# SKAARDUINO_v4_1.net
KiCad netlist of a schematic drawn in EAGLE
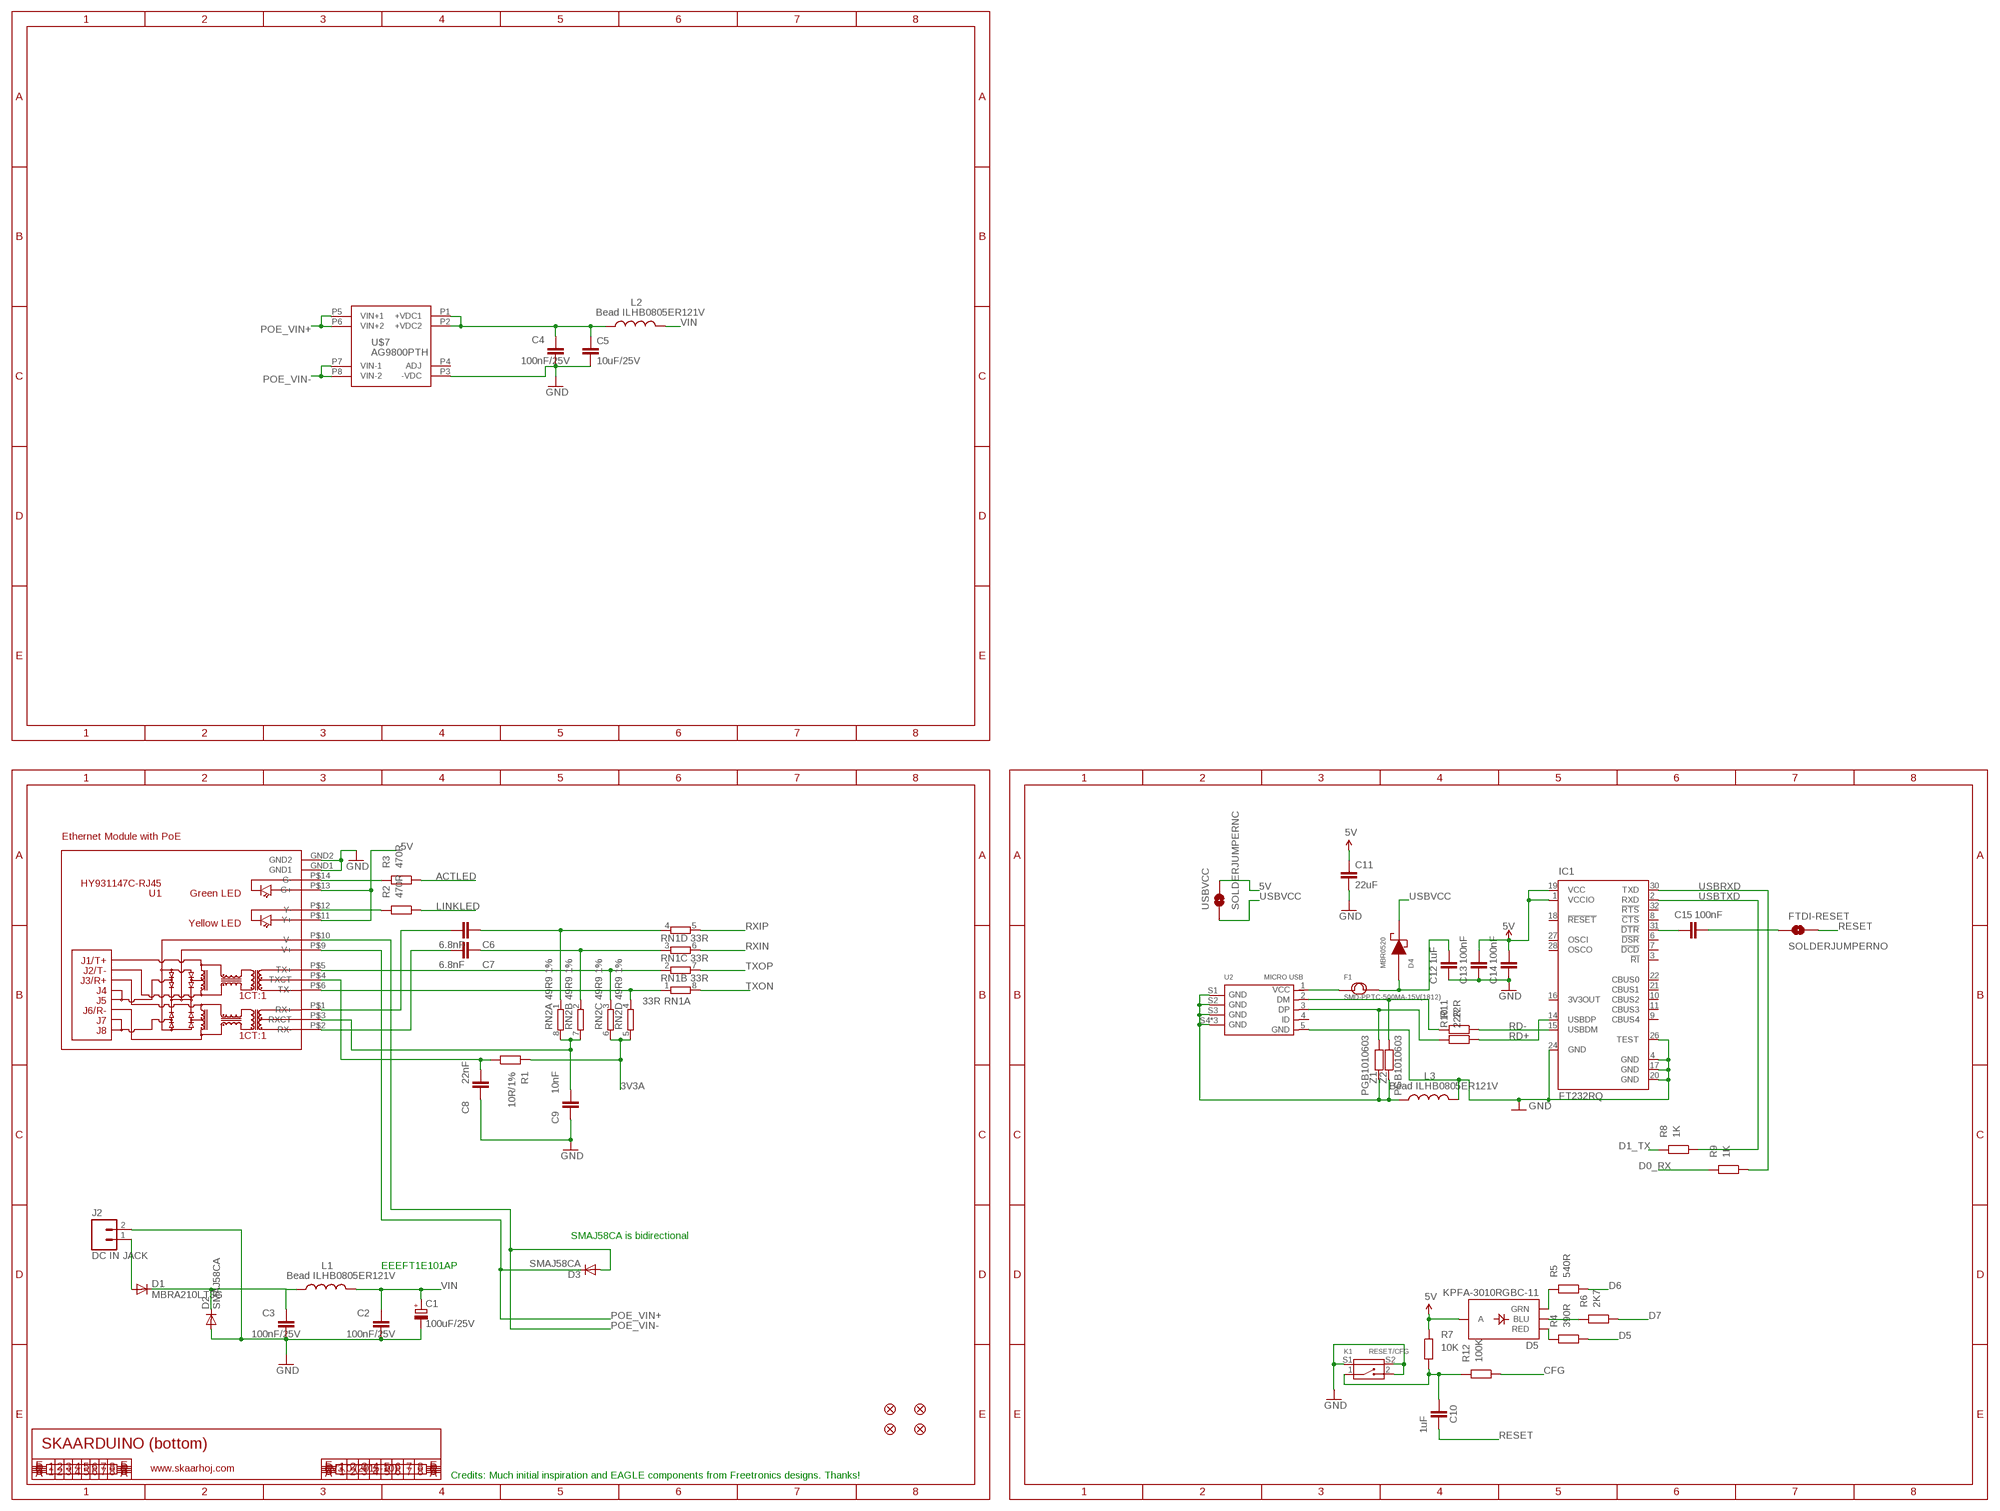
[diagram p0: schematic, sheet 1]
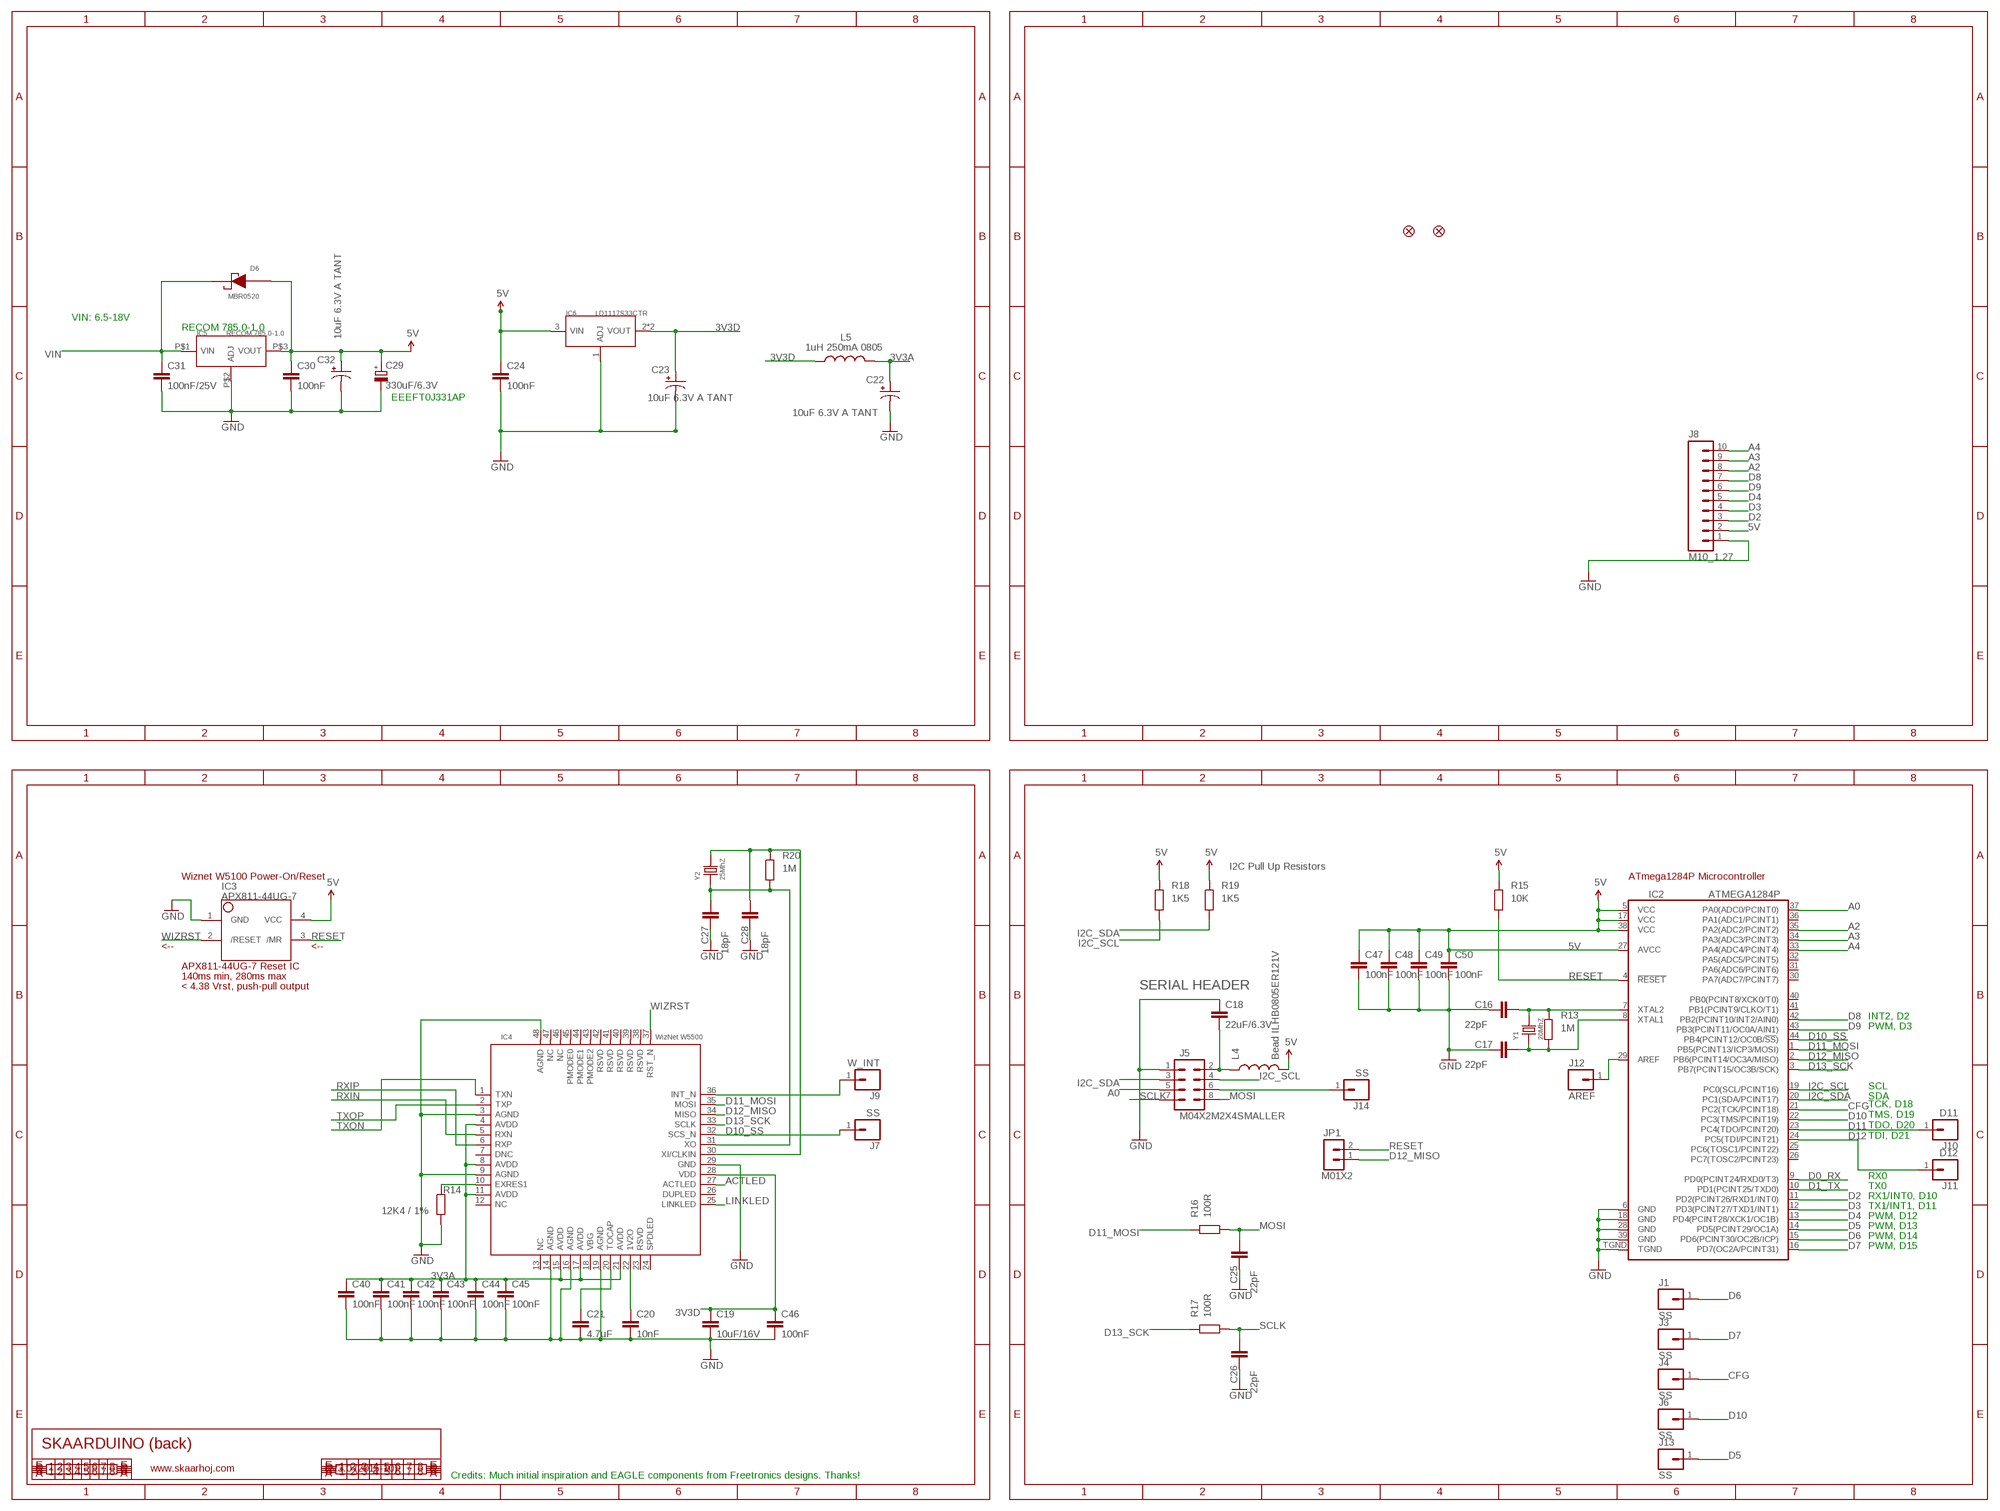
[diagram p1: schematic, sheet 2]

(export (version "E")
  (design (tool "Eeschema 10.0.6"))
  (components
    (comp (ref "C1")
      (value "100uF/25V")
      (footprint "eagle-import:PANASONIC_D")
      (libsource (lib "eagle-import") (part "CPOL-EUD"))
    )
    (comp (ref "C2")
      (value "100nF/25V")
      (footprint "eagle-import:C0402")
      (libsource (lib "eagle-import") (part "CAP0402"))
    )
    (comp (ref "C3")
      (value "100nF/25V")
      (footprint "eagle-import:C0402")
      (libsource (lib "eagle-import") (part "CAP0402"))
    )
    (comp (ref "C4")
      (value "100nF/25V")
      (footprint "eagle-import:C0402")
      (libsource (lib "eagle-import") (part "CAP0402"))
    )
    (comp (ref "C5")
      (value "10uF/25V")
      (footprint "eagle-import:0805")
      (libsource (lib "eagle-import") (part "CAP0805"))
    )
    (comp (ref "C6")
      (value "6.8nF")
      (footprint "eagle-import:0402C")
      (libsource (lib "eagle-import") (part "C-EU0402C"))
    )
    (comp (ref "C7")
      (value "6.8nF")
      (footprint "eagle-import:0402C")
      (libsource (lib "eagle-import") (part "C-EU0402C"))
    )
    (comp (ref "C8")
      (value "22nF")
      (footprint "eagle-import:0402C")
      (libsource (lib "eagle-import") (part "C-EU0402C"))
    )
    (comp (ref "C9")
      (value "10nF")
      (footprint "eagle-import:0402C")
      (libsource (lib "eagle-import") (part "C-EU0402C"))
    )
    (comp (ref "C10")
      (value "1uF")
      (footprint "eagle-import:0402C")
      (libsource (lib "eagle-import") (part "C-EU0402C"))
    )
    (comp (ref "C11")
      (value "22uF")
      (footprint "eagle-import:0805")
      (libsource (lib "eagle-import") (part "CAP0805"))
    )
    (comp (ref "C12")
      (value "1uF")
      (footprint "eagle-import:0402C")
      (libsource (lib "eagle-import") (part "C-EU0402C"))
    )
    (comp (ref "C13")
      (value "100nF")
      (footprint "eagle-import:0402C")
      (libsource (lib "eagle-import") (part "C-EU0402C"))
    )
    (comp (ref "C14")
      (value "100nF")
      (footprint "eagle-import:0402C")
      (libsource (lib "eagle-import") (part "C-EU0402C"))
    )
    (comp (ref "C15")
      (value "100nF")
      (footprint "eagle-import:0402C")
      (libsource (lib "eagle-import") (part "C-EU0402C"))
    )
    (comp (ref "D1")
      (value "MBRA210LT3G")
      (footprint "eagle-import:SMA-DIODE")
      (libsource (lib "eagle-import") (part "DIODESMA"))
    )
    (comp (ref "D2")
      (value "SMAJ58CA")
      (footprint "eagle-import:SMA-DIODE")
      (libsource (lib "eagle-import") (part "DIODESMA"))
    )
    (comp (ref "D3")
      (value "SMAJ58CA")
      (footprint "eagle-import:SMA-DIODE")
      (libsource (lib "eagle-import") (part "DIODESMA"))
    )
    (comp (ref "D4")
      (value "MBR0520")
      (footprint "eagle-import:SOD-123")
      (libsource (lib "eagle-import") (part "MBR0520"))
    )
    (comp (ref "D5")
      (value "KPFA-3010RGBC-11")
      (footprint "eagle-import:LED-TRICOLOR-SMD")
      (libsource (lib "eagle-import") (part "LED-TRICOLOR"))
    )
    (comp (ref "F1")
      (value "SMD-PPTC-500MA-15V(1812)")
      (footprint "eagle-import:F1812")
      (libsource (lib "eagle-import") (part "SMD-PPTC-500MA-15V(1812)"))
    )
    (comp (ref "FID1")
      (value "FIDUCIAL1X2.5")
      (footprint "eagle-import:FIDUCIAL-1X2.5")
      (libsource (lib "eagle-import") (part "FIDUCIAL1X2.5"))
    )
    (comp (ref "FID2")
      (value "FIDUCIAL1X2.5")
      (footprint "eagle-import:FIDUCIAL-1X2.5")
      (libsource (lib "eagle-import") (part "FIDUCIAL1X2.5"))
    )
    (comp (ref "FID3")
      (value "FIDUCIAL1X2.5")
      (footprint "eagle-import:FIDUCIAL-1X2.5")
      (libsource (lib "eagle-import") (part "FIDUCIAL1X2.5"))
    )
    (comp (ref "FID4")
      (value "FIDUCIAL1X2.5")
      (footprint "eagle-import:FIDUCIAL-1X2.5")
      (libsource (lib "eagle-import") (part "FIDUCIAL1X2.5"))
    )
    (comp (ref "FTDI-RESET")
      (value "SOLDERJUMPERNO")
      (footprint "eagle-import:SJ_2S-NO")
      (libsource (lib "eagle-import") (part "SOLDERJUMPERNO"))
    )
    (comp (ref "IC1")
      (value "FT232RQ")
      (footprint "eagle-import:QFN32")
      (libsource (lib "eagle-import") (part "FT232RQ"))
    )
    (comp (ref "J2")
      (value "DC IN JACK")
      (footprint "eagle-import:1X02")
      (libsource (lib "eagle-import") (part "M02PTH"))
    )
    (comp (ref "K1")
      (value "RESET/CFG")
      (footprint "eagle-import:SW4-SMD-7.0X3.5X3.5MM-90D")
      (fields (field (name "MPN") "TS-1188E"))
      (libsource (lib "eagle-import") (part "SMD-BUTTON-2+2P"))
    )
    (comp (ref "L1")
      (value "Bead ILHB0805ER121V")
      (footprint "eagle-import:L2012C")
      (libsource (lib "eagle-import") (part "L-USL2012C"))
    )
    (comp (ref "L2")
      (value "Bead ILHB0805ER121V")
      (footprint "eagle-import:L2012C")
      (libsource (lib "eagle-import") (part "L-USL2012C"))
    )
    (comp (ref "L3")
      (value "Bead ILHB0805ER121V")
      (footprint "eagle-import:L2012C")
      (libsource (lib "eagle-import") (part "L-USL2012C"))
    )
    (comp (ref "R1")
      (value "10R/1%")
      (footprint "eagle-import:0402")
      (libsource (lib "eagle-import") (part "freetronics-jon_RESISTOR0402"))
    )
    (comp (ref "R2")
      (value "470R")
      (footprint "eagle-import:0402")
      (libsource (lib "eagle-import") (part "freetronics-jon_RESISTOR0402"))
    )
    (comp (ref "R3")
      (value "470R")
      (footprint "eagle-import:0402")
      (libsource (lib "eagle-import") (part "freetronics-jon_RESISTOR0402"))
    )
    (comp (ref "R4")
      (value "390R")
      (footprint "eagle-import:0402")
      (libsource (lib "eagle-import") (part "freetronics-jon_RESISTOR0402"))
    )
    (comp (ref "R5")
      (value "540R")
      (footprint "eagle-import:0402")
      (libsource (lib "eagle-import") (part "freetronics-jon_RESISTOR0402"))
    )
    (comp (ref "R6")
      (value "2K7")
      (footprint "eagle-import:0402")
      (libsource (lib "eagle-import") (part "freetronics-jon_RESISTOR0402"))
    )
    (comp (ref "R7")
      (value "10K")
      (footprint "eagle-import:0402")
      (libsource (lib "eagle-import") (part "freetronics-jon_RESISTOR0402"))
    )
    (comp (ref "R8")
      (value "1K")
      (footprint "eagle-import:0402")
      (libsource (lib "eagle-import") (part "freetronics-jon_RESISTOR0402"))
    )
    (comp (ref "R9")
      (value "1K")
      (footprint "eagle-import:0402")
      (libsource (lib "eagle-import") (part "freetronics-jon_RESISTOR0402"))
    )
    (comp (ref "R10")
      (value "22R")
      (footprint "eagle-import:0402")
      (libsource (lib "eagle-import") (part "freetronics-jon_RESISTOR0402"))
    )
    (comp (ref "R11")
      (value "22R")
      (footprint "eagle-import:0402")
      (libsource (lib "eagle-import") (part "freetronics-jon_RESISTOR0402"))
    )
    (comp (ref "R12")
      (value "100K")
      (footprint "eagle-import:0402")
      (libsource (lib "eagle-import") (part "freetronics-jon_RESISTOR0402"))
    )
    (comp (ref "RN1")
      (value "33R")
      (footprint "eagle-import:CAY16")
      (libsource (lib "eagle-import") (part "4R-NCAY16"))
    )
    (comp (ref "RN2")
      (value "49R9 1%")
      (footprint "eagle-import:CAY16")
      (libsource (lib "eagle-import") (part "4R-NCAY16"))
    )
    (comp (ref "U$7")
      (value "AG9800PTH")
      (footprint "eagle-import:AG9800PTH")
      (libsource (lib "eagle-import") (part "AG9800PTH"))
    )
    (comp (ref "U1")
      (value "HY931147C-RJ45")
      (footprint "eagle-import:HY931147C")
      (libsource (lib "eagle-import") (part "HY931147C-RJ45"))
    )
    (comp (ref "U2")
      (value "MICRO USB")
      (footprint "eagle-import:MICRO-USB5+4P-SMD-0.65-B")
      (fields (field (name "MPN") "ST-USB-001G"))
      (libsource (lib "eagle-import") (part "MICRO-USB-SMD-B-WITHOUT-POST-W/P(ST-USB-001G)"))
    )
    (comp (ref "USBVCC")
      (value "SOLDERJUMPERNC")
      (footprint "eagle-import:SJ_2S")
      (libsource (lib "eagle-import") (part "SOLDERJUMPERNC"))
    )
    (comp (ref "Z1")
      (value "PGB1010603")
      (footprint "eagle-import:C0402")
      (libsource (lib "eagle-import") (part "RESISTOR0402"))
    )
    (comp (ref "Z2")
      (value "PGB1010603")
      (footprint "eagle-import:C0402")
      (libsource (lib "eagle-import") (part "RESISTOR0402"))
    )
    (comp (ref "C16")
      (value "22pF")
      (footprint "eagle-import:0402C")
      (libsource (lib "eagle-import") (part "C-EU0402C"))
    )
    (comp (ref "C17")
      (value "22pF")
      (footprint "eagle-import:0402C")
      (libsource (lib "eagle-import") (part "C-EU0402C"))
    )
    (comp (ref "C18")
      (value "22uF/6.3V")
      (footprint "eagle-import:0805")
      (libsource (lib "eagle-import") (part "CAP0805"))
    )
    (comp (ref "C19")
      (value "10uF/16V")
      (footprint "eagle-import:0805")
      (libsource (lib "eagle-import") (part "CAP0805"))
    )
    (comp (ref "C20")
      (value "10nF")
      (footprint "eagle-import:0402C")
      (libsource (lib "eagle-import") (part "C-EU0402C"))
    )
    (comp (ref "C21")
      (value "4.7uF")
      (footprint "eagle-import:0805")
      (libsource (lib "eagle-import") (part "CAP0805"))
    )
    (comp (ref "C22")
      (value "10uF 6.3V A TANT")
      (footprint "eagle-import:EIA3216")
      (libsource (lib "eagle-import") (part "CAP_POL1206"))
    )
    (comp (ref "C23")
      (value "10uF 6.3V A TANT")
      (footprint "eagle-import:EIA3216")
      (libsource (lib "eagle-import") (part "CAP_POL1206"))
    )
    (comp (ref "C24")
      (value "100nF")
      (footprint "eagle-import:0402C")
      (libsource (lib "eagle-import") (part "C-EU0402C"))
    )
    (comp (ref "C25")
      (value "22pF")
      (footprint "eagle-import:0402C")
      (libsource (lib "eagle-import") (part "C-EU0402C"))
    )
    (comp (ref "C26")
      (value "22pF")
      (footprint "eagle-import:0402C")
      (libsource (lib "eagle-import") (part "C-EU0402C"))
    )
    (comp (ref "C27")
      (value "18pF")
      (footprint "eagle-import:0402C")
      (libsource (lib "eagle-import") (part "C-EU0402C"))
    )
    (comp (ref "C28")
      (value "18pF")
      (footprint "eagle-import:0402C")
      (libsource (lib "eagle-import") (part "C-EU0402C"))
    )
    (comp (ref "C29")
      (value "330uF/6.3V")
      (footprint "eagle-import:PANASONIC_D")
      (libsource (lib "eagle-import") (part "CPOL-EUD"))
    )
    (comp (ref "C30")
      (value "100nF")
      (footprint "eagle-import:0402C")
      (libsource (lib "eagle-import") (part "C-EU0402C"))
    )
    (comp (ref "C31")
      (value "100nF/25V")
      (footprint "eagle-import:0402C")
      (libsource (lib "eagle-import") (part "C-EU0402C"))
    )
    (comp (ref "C32")
      (value "10uF 6.3V A TANT")
      (footprint "eagle-import:EIA3216")
      (libsource (lib "eagle-import") (part "CAP_POL1206"))
    )
    (comp (ref "C40")
      (value "100nF")
      (footprint "eagle-import:0402C")
      (libsource (lib "eagle-import") (part "C-EU0402C"))
    )
    (comp (ref "C41")
      (value "100nF")
      (footprint "eagle-import:0402C")
      (libsource (lib "eagle-import") (part "C-EU0402C"))
    )
    (comp (ref "C42")
      (value "100nF")
      (footprint "eagle-import:0402C")
      (libsource (lib "eagle-import") (part "C-EU0402C"))
    )
    (comp (ref "C43")
      (value "100nF")
      (footprint "eagle-import:0402C")
      (libsource (lib "eagle-import") (part "C-EU0402C"))
    )
    (comp (ref "C44")
      (value "100nF")
      (footprint "eagle-import:0402C")
      (libsource (lib "eagle-import") (part "C-EU0402C"))
    )
    (comp (ref "C45")
      (value "100nF")
      (footprint "eagle-import:0402C")
      (libsource (lib "eagle-import") (part "C-EU0402C"))
    )
    (comp (ref "C46")
      (value "100nF")
      (footprint "eagle-import:0402C")
      (libsource (lib "eagle-import") (part "C-EU0402C"))
    )
    (comp (ref "C47")
      (value "100nF")
      (footprint "eagle-import:0402C")
      (libsource (lib "eagle-import") (part "C-EU0402C"))
    )
    (comp (ref "C48")
      (value "100nF")
      (footprint "eagle-import:0402C")
      (libsource (lib "eagle-import") (part "C-EU0402C"))
    )
    (comp (ref "C49")
      (value "100nF")
      (footprint "eagle-import:0402C")
      (libsource (lib "eagle-import") (part "C-EU0402C"))
    )
    (comp (ref "C50")
      (value "100nF")
      (footprint "eagle-import:0402C")
      (libsource (lib "eagle-import") (part "C-EU0402C"))
    )
    (comp (ref "D6")
      (value "MBR0520")
      (footprint "eagle-import:SOD-123")
      (libsource (lib "eagle-import") (part "MBR0520"))
    )
    (comp (ref "FID5")
      (value "FIDUCIAL1X2.5")
      (footprint "eagle-import:FIDUCIAL-1X2.5")
      (libsource (lib "eagle-import") (part "FIDUCIAL1X2.5"))
    )
    (comp (ref "FID8")
      (value "FIDUCIAL1X2.5")
      (footprint "eagle-import:FIDUCIAL-1X2.5")
      (libsource (lib "eagle-import") (part "FIDUCIAL1X2.5"))
    )
    (comp (ref "IC2")
      (value "ATMEGA1284P")
      (footprint "eagle-import:QFN-44M1")
      (libsource (lib "eagle-import") (part "ATMEGA1284P"))
    )
    (comp (ref "IC3")
      (value "APX811-44UG-7")
      (footprint "eagle-import:SOT143-R")
      (libsource (lib "eagle-import") (part "APX81X-RESET-IC"))
    )
    (comp (ref "IC4")
      (value "WizNet W5500")
      (footprint "eagle-import:LQFP-48")
      (libsource (lib "eagle-import") (part "DRIVER-W5500"))
    )
    (comp (ref "IC5")
      (value "RECOM 785.0-1.0")
      (footprint "eagle-import:RECOM_785.0-1.0")
      (libsource (lib "eagle-import") (part "PMIC-LM317EMP"))
    )
    (comp (ref "IC6")
      (value "LD1117S33CTR")
      (footprint "eagle-import:SOT-223")
      (libsource (lib "eagle-import") (part "PMIC-LM317EMP-310030006"))
    )
    (comp (ref "J1")
      (value "SS")
      (footprint "eagle-import:M1X1")
      (libsource (lib "eagle-import") (part "M1X1TEST"))
    )
    (comp (ref "J3")
      (value "SS")
      (footprint "eagle-import:M1X1")
      (libsource (lib "eagle-import") (part "M1X1TEST"))
    )
    (comp (ref "J4")
      (value "SS")
      (footprint "eagle-import:M1X1")
      (libsource (lib "eagle-import") (part "M1X1TEST"))
    )
    (comp (ref "J5")
      (value "M04X2M2X4SMALLER")
      (footprint "eagle-import:M2X4SMALLER")
      (libsource (lib "eagle-import") (part "M04X2M2X4SMALLER"))
    )
    (comp (ref "J6")
      (value "SS")
      (footprint "eagle-import:M1X1")
      (libsource (lib "eagle-import") (part "M1X1TEST"))
    )
    (comp (ref "J7")
      (value "SS")
      (footprint "eagle-import:M1X1")
      (libsource (lib "eagle-import") (part "M1X1TEST"))
    )
    (comp (ref "J8")
      (value "M10_1.27")
      (footprint "eagle-import:M10X1")
      (libsource (lib "eagle-import") (part "M10_1.27"))
    )
    (comp (ref "J9")
      (value "W_INT")
      (footprint "eagle-import:M1X1")
      (libsource (lib "eagle-import") (part "M1X1TEST"))
    )
    (comp (ref "J10")
      (value "D11")
      (footprint "eagle-import:M1X1")
      (libsource (lib "eagle-import") (part "M1X1TEST"))
    )
    (comp (ref "J11")
      (value "D12")
      (footprint "eagle-import:M1X1")
      (libsource (lib "eagle-import") (part "M1X1TEST"))
    )
    (comp (ref "J12")
      (value "AREF")
      (footprint "eagle-import:M1X1")
      (libsource (lib "eagle-import") (part "M1X1TEST"))
    )
    (comp (ref "J13")
      (value "SS")
      (footprint "eagle-import:M1X1")
      (libsource (lib "eagle-import") (part "M1X1TEST"))
    )
    (comp (ref "J14")
      (value "SS")
      (footprint "eagle-import:M1X1")
      (libsource (lib "eagle-import") (part "M1X1TEST"))
    )
    (comp (ref "JP1")
      (value "M01X2")
      (footprint "eagle-import:M2X1SMALLER")
      (libsource (lib "eagle-import") (part "M01X2"))
    )
    (comp (ref "L4")
      (value "Bead ILHB0805ER121V")
      (footprint "eagle-import:0805")
      (libsource (lib "eagle-import") (part "INDUCTOR0805"))
    )
    (comp (ref "L5")
      (value "1uH 250mA 0805")
      (footprint "eagle-import:L2012C")
      (libsource (lib "eagle-import") (part "L-USL2012C"))
    )
    (comp (ref "R13")
      (value "1M")
      (footprint "eagle-import:0402")
      (libsource (lib "eagle-import") (part "freetronics-jon_RESISTOR0402"))
    )
    (comp (ref "R14")
      (value "12K4 / 1%")
      (footprint "eagle-import:0402")
      (libsource (lib "eagle-import") (part "freetronics-jon_RESISTOR0402"))
    )
    (comp (ref "R15")
      (value "10K")
      (footprint "eagle-import:0402")
      (libsource (lib "eagle-import") (part "freetronics-jon_RESISTOR0402"))
    )
    (comp (ref "R16")
      (value "100R")
      (footprint "eagle-import:0402")
      (libsource (lib "eagle-import") (part "freetronics-jon_RESISTOR0402"))
    )
    (comp (ref "R17")
      (value "100R")
      (footprint "eagle-import:0402")
      (libsource (lib "eagle-import") (part "freetronics-jon_RESISTOR0402"))
    )
    (comp (ref "R18")
      (value "1K5")
      (footprint "eagle-import:0402")
      (libsource (lib "eagle-import") (part "freetronics-jon_RESISTOR0402"))
    )
    (comp (ref "R19")
      (value "1K5")
      (footprint "eagle-import:0402")
      (libsource (lib "eagle-import") (part "freetronics-jon_RESISTOR0402"))
    )
    (comp (ref "R20")
      (value "1M")
      (footprint "eagle-import:0402")
      (libsource (lib "eagle-import") (part "freetronics-jon_RESISTOR0402"))
    )
    (comp (ref "Y1")
      (value "20MhZ")
      (footprint "eagle-import:X2-SMD-5.0X3.2X1.3MM")
      (fields (field (name "MPN") "X053201602002"))
      (libsource (lib "eagle-import") (part "SMD-CRYSTAL-16MHZ-8PF-20PPM-40R(2P-5.0X3.2MM)"))
    )
    (comp (ref "Y2")
      (value "25MhZ")
      (footprint "eagle-import:X2-SMD-5.0X3.2X1.3MM")
      (fields (field (name "MPN") "X053201602002"))
      (libsource (lib "eagle-import") (part "SMD-CRYSTAL-16MHZ-8PF-20PPM-40R(2P-5.0X3.2MM)"))
    )
  )
  (nets
    (net (code "1") (name "3V3A") (class "Default")
      (node (ref "C22") (pin "A") (pinfunction "+_A") (pintype "passive"))
      (node (ref "C40") (pin "1") (pinfunction "1_1") (pintype "passive"))
      (node (ref "C41") (pin "1") (pinfunction "1_1") (pintype "passive"))
      (node (ref "C42") (pin "1") (pinfunction "1_1") (pintype "passive"))
      (node (ref "C43") (pin "1") (pinfunction "1_1") (pintype "passive"))
      (node (ref "C44") (pin "1") (pinfunction "1_1") (pintype "passive"))
      (node (ref "C45") (pin "1") (pinfunction "1_1") (pintype "passive"))
      (node (ref "IC4") (pin "11") (pinfunction "AVDD_11") (pintype "passive"))
      (node (ref "IC4") (pin "15") (pinfunction "AVDD_15") (pintype "passive"))
      (node (ref "IC4") (pin "17") (pinfunction "AVDD_17") (pintype "passive"))
      (node (ref "IC4") (pin "21") (pinfunction "AVDD_21") (pintype "passive"))
      (node (ref "IC4") (pin "4") (pinfunction "AVDD_4") (pintype "passive"))
      (node (ref "IC4") (pin "8") (pinfunction "AVDD_8") (pintype "passive"))
      (node (ref "L5") (pin "2") (pinfunction "2_2") (pintype "passive"))
      (node (ref "R1") (pin "2") (pinfunction "2_2") (pintype "passive"))
      (node (ref "RN2") (pin "5") (pinfunction "2_5") (pintype "passive"))
      (node (ref "RN2") (pin "6") (pinfunction "2_6") (pintype "passive"))
    )
    (net (code "2") (name "3V3D") (class "Default")
      (node (ref "C19") (pin "1") (pinfunction "1_1") (pintype "passive"))
      (node (ref "C23") (pin "A") (pinfunction "+_A") (pintype "passive"))
      (node (ref "C46") (pin "1") (pinfunction "1_1") (pintype "passive"))
      (node (ref "IC4") (pin "28") (pinfunction "VDD_28") (pintype "passive"))
      (node (ref "IC6") (pin "2") (pinfunction "VOUT_2") (pintype "bidirectional"))
      (node (ref "IC6") (pin "TER") (pinfunction "VOUT_TER") (pintype "bidirectional"))
      (node (ref "L5") (pin "1") (pinfunction "1_1") (pintype "passive"))
    )
    (net (code "3") (name "5V") (class "Default")
      (node (ref "C11") (pin "1") (pinfunction "1_1") (pintype "passive"))
      (node (ref "C13") (pin "2") (pinfunction "2_2") (pintype "passive"))
      (node (ref "C14") (pin "2") (pinfunction "2_2") (pintype "passive"))
      (node (ref "C24") (pin "1") (pinfunction "1_1") (pintype "passive"))
      (node (ref "C29") (pin "+") (pinfunction "+_+") (pintype "passive"))
      (node (ref "C30") (pin "1") (pinfunction "1_1") (pintype "passive"))
      (node (ref "C32") (pin "A") (pinfunction "+_A") (pintype "passive"))
      (node (ref "C47") (pin "1") (pinfunction "1_1") (pintype "passive"))
      (node (ref "C48") (pin "1") (pinfunction "1_1") (pintype "passive"))
      (node (ref "C49") (pin "1") (pinfunction "1_1") (pintype "passive"))
      (node (ref "C50") (pin "1") (pinfunction "1_1") (pintype "passive"))
      (node (ref "D5") (pin "A") (pinfunction "A_A") (pintype "bidirectional"))
      (node (ref "D6") (pin "2") (pinfunction "AN_2") (pintype "passive"))
      (node (ref "IC1") (pin "1") (pinfunction "VCCIO_1") (pintype "power_in"))
      (node (ref "IC1") (pin "19") (pinfunction "VCC_19") (pintype "power_in"))
      (node (ref "IC2") (pin "17") (pinfunction "VCC_17") (pintype "bidirectional"))
      (node (ref "IC2") (pin "27") (pinfunction "AVCC_27") (pintype "bidirectional"))
      (node (ref "IC2") (pin "38") (pinfunction "VCC_38") (pintype "bidirectional"))
      (node (ref "IC2") (pin "5") (pinfunction "VCC_5") (pintype "bidirectional"))
      (node (ref "IC3") (pin "4") (pinfunction "VCC_4") (pintype "power_in"))
      (node (ref "IC5") (pin "P$3") (pinfunction "VOUT_P$3") (pintype "bidirectional"))
      (node (ref "IC6") (pin "3") (pinfunction "VIN_3") (pintype "bidirectional"))
      (node (ref "J8") (pin "2") (pinfunction "2_2") (pintype "passive"))
      (node (ref "L4") (pin "2") (pinfunction "2_2") (pintype "passive"))
      (node (ref "R15") (pin "2") (pinfunction "2_2") (pintype "passive"))
      (node (ref "R18") (pin "2") (pinfunction "2_2") (pintype "passive"))
      (node (ref "R19") (pin "2") (pinfunction "2_2") (pintype "passive"))
      (node (ref "R7") (pin "2") (pinfunction "2_2") (pintype "passive"))
      (node (ref "U1") (pin "P$11") (pinfunction "Y+_P$11") (pintype "bidirectional"))
      (node (ref "U1") (pin "P$13") (pinfunction "G+_P$13") (pintype "bidirectional"))
      (node (ref "USBVCC") (pin "2") (pinfunction "2_2") (pintype "passive"))
    )
    (net (code "4") (name "A0") (class "Default")
      (node (ref "IC2") (pin "37") (pinfunction "PA0(ADC0/PCINT0)_37") (pintype "bidirectional"))
      (node (ref "J5") (pin "5") (pinfunction "5_5") (pintype "passive"))
    )
    (net (code "5") (name "A2") (class "Default")
      (node (ref "IC2") (pin "35") (pinfunction "PA2(ADC2/PCINT2)_35") (pintype "bidirectional"))
      (node (ref "J8") (pin "8") (pinfunction "8_8") (pintype "passive"))
    )
    (net (code "6") (name "A3") (class "Default")
      (node (ref "IC2") (pin "34") (pinfunction "PA3(ADC3/PCINT3)_34") (pintype "bidirectional"))
      (node (ref "J8") (pin "9") (pinfunction "9_9") (pintype "passive"))
    )
    (net (code "7") (name "A4") (class "Default")
      (node (ref "IC2") (pin "33") (pinfunction "PA4(ADC4/PCINT4)_33") (pintype "bidirectional"))
      (node (ref "J8") (pin "10") (pinfunction "10_10") (pintype "passive"))
    )
    (net (code "8") (name "ACTLED") (class "Default")
      (node (ref "IC4") (pin "27") (pinfunction "ACTLED_27") (pintype "passive"))
      (node (ref "R3") (pin "1") (pinfunction "1_1") (pintype "passive"))
    )
    (net (code "9") (name "CFG") (class "Default")
      (node (ref "IC2") (pin "21") (pinfunction "PC2(TCK/PCINT18)_21") (pintype "bidirectional"))
      (node (ref "J4") (pin "1") (pinfunction "5_1") (pintype "passive"))
      (node (ref "R12") (pin "1") (pinfunction "1_1") (pintype "passive"))
    )
    (net (code "10") (name "D0_RX") (class "Default")
      (node (ref "IC2") (pin "9") (pinfunction "PD0(PCINT24/RXD0/T3)_9") (pintype "bidirectional"))
      (node (ref "R9") (pin "2") (pinfunction "2_2") (pintype "passive"))
    )
    (net (code "11") (name "D1_TX") (class "Default")
      (node (ref "IC2") (pin "10") (pinfunction "PD1(PCINT25/TXD0)_10") (pintype "bidirectional"))
      (node (ref "R8") (pin "2") (pinfunction "2_2") (pintype "passive"))
    )
    (net (code "12") (name "D2") (class "Default")
      (node (ref "IC2") (pin "11") (pinfunction "PD2(PCINT26/RXD1/INT0)_11") (pintype "bidirectional"))
      (node (ref "J8") (pin "3") (pinfunction "3_3") (pintype "passive"))
    )
    (net (code "13") (name "D3") (class "Default")
      (node (ref "IC2") (pin "12") (pinfunction "PD3(PCINT27/TXD1/INT1)_12") (pintype "bidirectional"))
      (node (ref "J8") (pin "4") (pinfunction "4_4") (pintype "passive"))
    )
    (net (code "14") (name "D4") (class "Default")
      (node (ref "IC2") (pin "13") (pinfunction "PD4(PCINT28/XCK1/OC1B)_13") (pintype "bidirectional"))
      (node (ref "J8") (pin "5") (pinfunction "5_5") (pintype "passive"))
    )
    (net (code "15") (name "D5") (class "Default")
      (node (ref "IC2") (pin "14") (pinfunction "PD5(PCINT29/OC1A)_14") (pintype "bidirectional"))
      (node (ref "J13") (pin "1") (pinfunction "5_1") (pintype "passive"))
      (node (ref "R4") (pin "1") (pinfunction "1_1") (pintype "passive"))
    )
    (net (code "16") (name "D6") (class "Default")
      (node (ref "IC2") (pin "15") (pinfunction "PD6(PCINT30/OC2B/ICP)_15") (pintype "bidirectional"))
      (node (ref "J1") (pin "1") (pinfunction "5_1") (pintype "passive"))
      (node (ref "R5") (pin "1") (pinfunction "1_1") (pintype "passive"))
    )
    (net (code "17") (name "D7") (class "Default")
      (node (ref "IC2") (pin "16") (pinfunction "PD7(OC2A/PCINT31)_16") (pintype "bidirectional"))
      (node (ref "J3") (pin "1") (pinfunction "5_1") (pintype "passive"))
      (node (ref "R6") (pin "1") (pinfunction "1_1") (pintype "passive"))
    )
    (net (code "18") (name "D8") (class "Default")
      (node (ref "IC2") (pin "42") (pinfunction "PB2(PCINT10/INT2/AIN0)_42") (pintype "bidirectional"))
      (node (ref "J8") (pin "7") (pinfunction "7_7") (pintype "passive"))
    )
    (net (code "19") (name "D9") (class "Default")
      (node (ref "IC2") (pin "43") (pinfunction "PB3(PCINT11/OC0A/AIN1)_43") (pintype "bidirectional"))
      (node (ref "J8") (pin "6") (pinfunction "6_6") (pintype "passive"))
    )
    (net (code "20") (name "D10") (class "Default")
      (node (ref "IC2") (pin "22") (pinfunction "PC3(TMS/PCINT19)_22") (pintype "bidirectional"))
      (node (ref "J6") (pin "1") (pinfunction "5_1") (pintype "passive"))
    )
    (net (code "21") (name "D10_SS") (class "Default")
      (node (ref "IC2") (pin "44") (pinfunction "PB4(PCINT12/OC0B/~{SS})_44") (pintype "bidirectional"))
      (node (ref "IC4") (pin "32") (pinfunction "SCS_N_32") (pintype "passive"))
      (node (ref "J7") (pin "1") (pinfunction "5_1") (pintype "passive"))
    )
    (net (code "22") (name "D11") (class "Default")
      (node (ref "IC2") (pin "23") (pinfunction "PC4(TDO/PCINT20)_23") (pintype "bidirectional"))
      (node (ref "J10") (pin "1") (pinfunction "5_1") (pintype "passive"))
    )
    (net (code "23") (name "D11_MOSI") (class "Default")
      (node (ref "IC2") (pin "1") (pinfunction "PB5(PCINT13/ICP3/MOSI)_1") (pintype "bidirectional"))
      (node (ref "IC4") (pin "35") (pinfunction "MOSI_35") (pintype "passive"))
      (node (ref "R16") (pin "2") (pinfunction "2_2") (pintype "passive"))
    )
    (net (code "24") (name "D12") (class "Default")
      (node (ref "IC2") (pin "24") (pinfunction "PC5(TDI/PCINT21)_24") (pintype "bidirectional"))
      (node (ref "J11") (pin "1") (pinfunction "5_1") (pintype "passive"))
    )
    (net (code "25") (name "D12_MISO") (class "Default")
      (node (ref "IC2") (pin "2") (pinfunction "PB6(PCINT14/OC3A/MISO)_2") (pintype "bidirectional"))
      (node (ref "IC4") (pin "34") (pinfunction "MISO_34") (pintype "passive"))
      (node (ref "JP1") (pin "1") (pinfunction "1_1") (pintype "passive"))
    )
    (net (code "26") (name "D13_SCK") (class "Default")
      (node (ref "IC2") (pin "3") (pinfunction "PB7(PCINT15/OC3B/SCK)_3") (pintype "bidirectional"))
      (node (ref "IC4") (pin "33") (pinfunction "SCLK_33") (pintype "passive"))
      (node (ref "R17") (pin "2") (pinfunction "2_2") (pintype "passive"))
    )
    (net (code "27") (name "GND") (class "Default")
      (node (ref "C1") (pin "-") (pinfunction "-_-") (pintype "passive"))
      (node (ref "C11") (pin "2") (pinfunction "2_2") (pintype "passive"))
      (node (ref "C12") (pin "1") (pinfunction "1_1") (pintype "passive"))
      (node (ref "C13") (pin "1") (pinfunction "1_1") (pintype "passive"))
      (node (ref "C14") (pin "1") (pinfunction "1_1") (pintype "passive"))
      (node (ref "C16") (pin "1") (pinfunction "1_1") (pintype "passive"))
      (node (ref "C17") (pin "1") (pinfunction "1_1") (pintype "passive"))
      (node (ref "C18") (pin "1") (pinfunction "1_1") (pintype "passive"))
      (node (ref "C19") (pin "2") (pinfunction "2_2") (pintype "passive"))
      (node (ref "C2") (pin "2") (pinfunction "2_2") (pintype "passive"))
      (node (ref "C20") (pin "2") (pinfunction "2_2") (pintype "passive"))
      (node (ref "C21") (pin "2") (pinfunction "2_2") (pintype "passive"))
      (node (ref "C22") (pin "C") (pinfunction "-_C") (pintype "passive"))
      (node (ref "C23") (pin "C") (pinfunction "-_C") (pintype "passive"))
      (node (ref "C24") (pin "2") (pinfunction "2_2") (pintype "passive"))
      (node (ref "C25") (pin "1") (pinfunction "1_1") (pintype "passive"))
      (node (ref "C26") (pin "1") (pinfunction "1_1") (pintype "passive"))
      (node (ref "C27") (pin "1") (pinfunction "1_1") (pintype "passive"))
      (node (ref "C28") (pin "1") (pinfunction "1_1") (pintype "passive"))
      (node (ref "C29") (pin "-") (pinfunction "-_-") (pintype "passive"))
      (node (ref "C3") (pin "2") (pinfunction "2_2") (pintype "passive"))
      (node (ref "C30") (pin "2") (pinfunction "2_2") (pintype "passive"))
      (node (ref "C31") (pin "2") (pinfunction "2_2") (pintype "passive"))
      (node (ref "C32") (pin "C") (pinfunction "-_C") (pintype "passive"))
      (node (ref "C4") (pin "2") (pinfunction "2_2") (pintype "passive"))
      (node (ref "C40") (pin "2") (pinfunction "2_2") (pintype "passive"))
      (node (ref "C41") (pin "2") (pinfunction "2_2") (pintype "passive"))
      (node (ref "C42") (pin "2") (pinfunction "2_2") (pintype "passive"))
      (node (ref "C43") (pin "2") (pinfunction "2_2") (pintype "passive"))
      (node (ref "C44") (pin "2") (pinfunction "2_2") (pintype "passive"))
      (node (ref "C45") (pin "2") (pinfunction "2_2") (pintype "passive"))
      (node (ref "C46") (pin "2") (pinfunction "2_2") (pintype "passive"))
      (node (ref "C47") (pin "2") (pinfunction "2_2") (pintype "passive"))
      (node (ref "C48") (pin "2") (pinfunction "2_2") (pintype "passive"))
      (node (ref "C49") (pin "2") (pinfunction "2_2") (pintype "passive"))
      (node (ref "C5") (pin "2") (pinfunction "2_2") (pintype "passive"))
      (node (ref "C50") (pin "2") (pinfunction "2_2") (pintype "passive"))
      (node (ref "C8") (pin "1") (pinfunction "1_1") (pintype "passive"))
      (node (ref "C9") (pin "1") (pinfunction "1_1") (pintype "passive"))
      (node (ref "D2") (pin "A") (pinfunction "A_A") (pintype "passive"))
      (node (ref "IC1") (pin "17") (pinfunction "GND_17") (pintype "power_in"))
      (node (ref "IC1") (pin "20") (pinfunction "GND_20") (pintype "power_in"))
      (node (ref "IC1") (pin "24") (pinfunction "GND_24") (pintype "power_in"))
      (node (ref "IC1") (pin "26") (pinfunction "TEST_26") (pintype "input"))
      (node (ref "IC1") (pin "4") (pinfunction "GND_4") (pintype "power_in"))
      (node (ref "IC2") (pin "18") (pinfunction "GND_18") (pintype "bidirectional"))
      (node (ref "IC2") (pin "28") (pinfunction "GND_28") (pintype "bidirectional"))
      (node (ref "IC2") (pin "39") (pinfunction "GND_39") (pintype "bidirectional"))
      (node (ref "IC2") (pin "6") (pinfunction "GND_6") (pintype "bidirectional"))
      (node (ref "IC2") (pin "TGND") (pinfunction "TGND_TGND") (pintype "bidirectional"))
      (node (ref "IC3") (pin "1") (pinfunction "GND_1") (pintype "power_in"))
      (node (ref "IC4") (pin "14") (pinfunction "AGND_14") (pintype "passive"))
      (node (ref "IC4") (pin "16") (pinfunction "AGND_16") (pintype "passive"))
      (node (ref "IC4") (pin "19") (pinfunction "AGND_19") (pintype "passive"))
      (node (ref "IC4") (pin "29") (pinfunction "GND_29") (pintype "passive"))
      (node (ref "IC4") (pin "3") (pinfunction "AGND_3") (pintype "passive"))
      (node (ref "IC4") (pin "48") (pinfunction "AGND_48") (pintype "passive"))
      (node (ref "IC4") (pin "9") (pinfunction "AGND_9") (pintype "passive"))
      (node (ref "IC5") (pin "P$2") (pinfunction "ADJ_P$2") (pintype "bidirectional"))
      (node (ref "IC6") (pin "1") (pinfunction "ADJ_1") (pintype "bidirectional"))
      (node (ref "J2") (pin "2") (pinfunction "2_2") (pintype "passive"))
      (node (ref "J5") (pin "1") (pinfunction "1_1") (pintype "passive"))
      (node (ref "J8") (pin "1") (pinfunction "1_1") (pintype "passive"))
      (node (ref "K1") (pin "2") (pinfunction "2_2") (pintype "bidirectional"))
      (node (ref "K1") (pin "S1") (pinfunction "S1_S1") (pintype "bidirectional"))
      (node (ref "K1") (pin "S2") (pinfunction "S2_S2") (pintype "bidirectional"))
      (node (ref "L3") (pin "2") (pinfunction "2_2") (pintype "passive"))
      (node (ref "R14") (pin "1") (pinfunction "1_1") (pintype "passive"))
      (node (ref "U$7") (pin "P3") (pinfunction "-VDC_P3") (pintype "bidirectional"))
      (node (ref "U1") (pin "GND1") (pinfunction "GND1_GND1") (pintype "bidirectional"))
      (node (ref "U1") (pin "GND2") (pinfunction "GND2_GND2") (pintype "bidirectional"))
      (node (ref "U2") (pin "5") (pinfunction "GND_5") (pintype "bidirectional"))
    )
    (net (code "28") (name "I2C_SCL") (class "Default")
      (node (ref "IC2") (pin "19") (pinfunction "PC0(SCL/PCINT16)_19") (pintype "bidirectional"))
      (node (ref "J5") (pin "4") (pinfunction "4_4") (pintype "passive"))
      (node (ref "R18") (pin "1") (pinfunction "1_1") (pintype "passive"))
    )
    (net (code "29") (name "I2C_SDA") (class "Default")
      (node (ref "IC2") (pin "20") (pinfunction "PC1(SDA/PCINT17)_20") (pintype "bidirectional"))
      (node (ref "J5") (pin "3") (pinfunction "3_3") (pintype "passive"))
      (node (ref "R19") (pin "1") (pinfunction "1_1") (pintype "passive"))
    )
    (net (code "30") (name "LINKLED") (class "Default")
      (node (ref "IC4") (pin "25") (pinfunction "LINKLED_25") (pintype "passive"))
      (node (ref "R2") (pin "1") (pinfunction "1_1") (pintype "passive"))
    )
    (net (code "31") (name "MOSI") (class "Default")
      (node (ref "C25") (pin "2") (pinfunction "2_2") (pintype "passive"))
      (node (ref "J5") (pin "8") (pinfunction "8_8") (pintype "passive"))
      (node (ref "R16") (pin "1") (pinfunction "1_1") (pintype "passive"))
    )
    (net (code "32") (name "Net-(C3-Pad1)") (class "Default")
      (node (ref "C3") (pin "1") (pinfunction "1_1") (pintype "passive"))
      (node (ref "D1") (pin "C") (pinfunction "C_C") (pintype "passive"))
      (node (ref "D2") (pin "C") (pinfunction "C_C") (pintype "passive"))
      (node (ref "L1") (pin "1") (pinfunction "1_1") (pintype "passive"))
    )
    (net (code "33") (name "Net-(C10-Pad2)") (class "Default")
      (node (ref "C10") (pin "2") (pinfunction "2_2") (pintype "passive"))
      (node (ref "K1") (pin "1") (pinfunction "1_1") (pintype "bidirectional"))
      (node (ref "R12") (pin "2") (pinfunction "2_2") (pintype "passive"))
      (node (ref "R7") (pin "1") (pinfunction "1_1") (pintype "passive"))
    )
    (net (code "34") (name "Net-(C15-Pad2)") (class "Default")
      (node (ref "C15") (pin "2") (pinfunction "2_2") (pintype "passive"))
      (node (ref "FTDI-RESET") (pin "1") (pinfunction "1_1") (pintype "passive"))
    )
    (net (code "35") (name "Net-(C18-Pad2)") (class "Default")
      (node (ref "C18") (pin "2") (pinfunction "2_2") (pintype "passive"))
      (node (ref "J5") (pin "2") (pinfunction "2_2") (pintype "passive"))
      (node (ref "L4") (pin "1") (pinfunction "1_1") (pintype "passive"))
    )
    (net (code "36") (name "Net-(D1-PadA)") (class "Default")
      (node (ref "D1") (pin "A") (pinfunction "A_A") (pintype "passive"))
      (node (ref "J2") (pin "1") (pinfunction "1_1") (pintype "passive"))
    )
    (net (code "37") (name "Net-(D4-AN)") (class "Default")
      (node (ref "C12") (pin "2") (pinfunction "2_2") (pintype "passive"))
      (node (ref "D4") (pin "2") (pinfunction "AN_2") (pintype "passive"))
      (node (ref "F1") (pin "2") (pinfunction "2_2") (pintype "bidirectional"))
    )
    (net (code "38") (name "Net-(D5-BLU)") (class "Default")
      (node (ref "D5") (pin "B") (pinfunction "BLU_B") (pintype "bidirectional"))
      (node (ref "R6") (pin "2") (pinfunction "2_2") (pintype "passive"))
    )
    (net (code "39") (name "Net-(D5-GRN)") (class "Default")
      (node (ref "D5") (pin "G") (pinfunction "GRN_G") (pintype "bidirectional"))
      (node (ref "R5") (pin "2") (pinfunction "2_2") (pintype "passive"))
    )
    (net (code "40") (name "Net-(D5-RED)") (class "Default")
      (node (ref "D5") (pin "R") (pinfunction "RED_R") (pintype "bidirectional"))
      (node (ref "R4") (pin "2") (pinfunction "2_2") (pintype "passive"))
    )
    (net (code "41") (name "Net-(IC1-~{DTR})") (class "Default")
      (node (ref "C15") (pin "1") (pinfunction "1_1") (pintype "passive"))
      (node (ref "IC1") (pin "31") (pinfunction "~{DTR}_31") (pintype "output"))
    )
    (net (code "42") (name "Net-(IC2-AREF)") (class "Default")
      (node (ref "IC2") (pin "29") (pinfunction "AREF_29") (pintype "bidirectional"))
      (node (ref "J12") (pin "1") (pinfunction "5_1") (pintype "passive"))
    )
    (net (code "43") (name "Net-(IC2-XTAL1)") (class "Default")
      (node (ref "C17") (pin "2") (pinfunction "2_2") (pintype "passive"))
      (node (ref "IC2") (pin "8") (pinfunction "XTAL1_8") (pintype "bidirectional"))
      (node (ref "R13") (pin "1") (pinfunction "1_1") (pintype "passive"))
      (node (ref "Y1") (pin "1") (pinfunction "1_1") (pintype "passive"))
    )
    (net (code "44") (name "Net-(IC2-XTAL2)") (class "Default")
      (node (ref "C16") (pin "2") (pinfunction "2_2") (pintype "passive"))
      (node (ref "IC2") (pin "7") (pinfunction "XTAL2_7") (pintype "bidirectional"))
      (node (ref "R13") (pin "2") (pinfunction "2_2") (pintype "passive"))
      (node (ref "Y1") (pin "2") (pinfunction "2_2") (pintype "passive"))
    )
    (net (code "45") (name "Net-(IC4-1V2O)") (class "Default")
      (node (ref "C20") (pin "1") (pinfunction "1_1") (pintype "passive"))
      (node (ref "IC4") (pin "22") (pinfunction "1V2O_22") (pintype "passive"))
    )
    (net (code "46") (name "Net-(IC4-EXRES1)") (class "Default")
      (node (ref "IC4") (pin "10") (pinfunction "EXRES1_10") (pintype "passive"))
      (node (ref "R14") (pin "2") (pinfunction "2_2") (pintype "passive"))
    )
    (net (code "47") (name "Net-(IC4-INT_N)") (class "Default")
      (node (ref "IC4") (pin "36") (pinfunction "INT_N_36") (pintype "passive"))
      (node (ref "J9") (pin "1") (pinfunction "5_1") (pintype "passive"))
    )
    (net (code "48") (name "Net-(IC4-TOCAP)") (class "Default")
      (node (ref "C21") (pin "1") (pinfunction "1_1") (pintype "passive"))
      (node (ref "IC4") (pin "20") (pinfunction "TOCAP_20") (pintype "passive"))
    )
    (net (code "49") (name "Net-(IC4-XI{slash}CLKIN)") (class "Default")
      (node (ref "C28") (pin "2") (pinfunction "2_2") (pintype "passive"))
      (node (ref "IC4") (pin "30") (pinfunction "XI/CLKIN_30") (pintype "passive"))
      (node (ref "R20") (pin "2") (pinfunction "2_2") (pintype "passive"))
      (node (ref "Y2") (pin "2") (pinfunction "2_2") (pintype "passive"))
    )
    (net (code "50") (name "Net-(IC4-XO)") (class "Default")
      (node (ref "C27") (pin "2") (pinfunction "2_2") (pintype "passive"))
      (node (ref "IC4") (pin "31") (pinfunction "XO_31") (pintype "passive"))
      (node (ref "R20") (pin "1") (pinfunction "1_1") (pintype "passive"))
      (node (ref "Y2") (pin "1") (pinfunction "1_1") (pintype "passive"))
    )
    (net (code "51") (name "Net-(J14-5)") (class "Default")
      (node (ref "J14") (pin "1") (pinfunction "5_1") (pintype "passive"))
      (node (ref "J5") (pin "6") (pinfunction "6_6") (pintype "passive"))
    )
    (net (code "52") (name "Net-(L3-Pad1)") (class "Default")
      (node (ref "L3") (pin "1") (pinfunction "1_1") (pintype "passive"))
      (node (ref "U2") (pin "S1") (pinfunction "GND_S1") (pintype "bidirectional"))
      (node (ref "U2") (pin "S2") (pinfunction "GND_S2") (pintype "bidirectional"))
      (node (ref "U2") (pin "S3") (pinfunction "GND_S3") (pintype "bidirectional"))
      (node (ref "U2") (pin "S4") (pinfunction "GND_S4") (pintype "bidirectional"))
      (node (ref "U2") (pin "S5") (pinfunction "GND_S5") (pintype "bidirectional"))
      (node (ref "U2") (pin "S6") (pinfunction "GND_S6") (pintype "bidirectional"))
      (node (ref "Z1") (pin "2") (pinfunction "2_2") (pintype "passive"))
      (node (ref "Z2") (pin "2") (pinfunction "2_2") (pintype "passive"))
    )
    (net (code "53") (name "Net-(RN1B-1)") (class "Default")
      (node (ref "RN1") (pin "2") (pinfunction "1_2") (pintype "passive"))
      (node (ref "RN2") (pin "3") (pinfunction "1_3") (pintype "passive"))
      (node (ref "U1") (pin "P$5") (pinfunction "TX+_P$5") (pintype "bidirectional"))
    )
    (net (code "54") (name "Net-(RN1C-1)") (class "Default")
      (node (ref "C7") (pin "1") (pinfunction "1_1") (pintype "passive"))
      (node (ref "RN1") (pin "3") (pinfunction "1_3") (pintype "passive"))
      (node (ref "RN2") (pin "2") (pinfunction "1_2") (pintype "passive"))
    )
    (net (code "55") (name "Net-(RN1D-1)") (class "Default")
      (node (ref "C6") (pin "1") (pinfunction "1_1") (pintype "passive"))
      (node (ref "RN1") (pin "4") (pinfunction "1_4") (pintype "passive"))
      (node (ref "RN2") (pin "1") (pinfunction "1_1") (pintype "passive"))
    )
    (net (code "56") (name "Net-(RN2A-2)") (class "Default")
      (node (ref "C9") (pin "2") (pinfunction "2_2") (pintype "passive"))
      (node (ref "RN2") (pin "7") (pinfunction "2_7") (pintype "passive"))
      (node (ref "RN2") (pin "8") (pinfunction "2_8") (pintype "passive"))
      (node (ref "U1") (pin "P$3") (pinfunction "RXCT_P$3") (pintype "bidirectional"))
    )
    (net (code "57") (name "Net-(RN2D-1)") (class "Default")
      (node (ref "RN1") (pin "1") (pinfunction "1_1") (pintype "passive"))
      (node (ref "RN2") (pin "4") (pinfunction "1_4") (pintype "passive"))
      (node (ref "U1") (pin "P$6") (pinfunction "TX-_P$6") (pintype "bidirectional"))
    )
    (net (code "58") (name "Net-(U$7-+VDC1)") (class "Default")
      (node (ref "C4") (pin "1") (pinfunction "1_1") (pintype "passive"))
      (node (ref "C5") (pin "1") (pinfunction "1_1") (pintype "passive"))
      (node (ref "L2") (pin "1") (pinfunction "1_1") (pintype "passive"))
      (node (ref "U$7") (pin "P1") (pinfunction "+VDC1_P1") (pintype "bidirectional"))
      (node (ref "U$7") (pin "P2") (pinfunction "+VDC2_P2") (pintype "bidirectional"))
    )
    (net (code "59") (name "Net-(U1-G-)") (class "Default")
      (node (ref "R3") (pin "2") (pinfunction "2_2") (pintype "passive"))
      (node (ref "U1") (pin "P$14") (pinfunction "G-_P$14") (pintype "bidirectional"))
    )
    (net (code "60") (name "Net-(U1-RX+)") (class "Default")
      (node (ref "C6") (pin "2") (pinfunction "2_2") (pintype "passive"))
      (node (ref "U1") (pin "P$1") (pinfunction "RX+_P$1") (pintype "bidirectional"))
    )
    (net (code "61") (name "Net-(U1-RX-)") (class "Default")
      (node (ref "C7") (pin "2") (pinfunction "2_2") (pintype "passive"))
      (node (ref "U1") (pin "P$2") (pinfunction "RX-_P$2") (pintype "bidirectional"))
    )
    (net (code "62") (name "Net-(U1-TXCT)") (class "Default")
      (node (ref "C8") (pin "2") (pinfunction "2_2") (pintype "passive"))
      (node (ref "R1") (pin "1") (pinfunction "1_1") (pintype "passive"))
      (node (ref "U1") (pin "P$4") (pinfunction "TXCT_P$4") (pintype "bidirectional"))
    )
    (net (code "63") (name "Net-(U1-Y-)") (class "Default")
      (node (ref "R2") (pin "2") (pinfunction "2_2") (pintype "passive"))
      (node (ref "U1") (pin "P$12") (pinfunction "Y-_P$12") (pintype "bidirectional"))
    )
    (net (code "64") (name "Net-(U2-DM)") (class "Default")
      (node (ref "R11") (pin "2") (pinfunction "2_2") (pintype "passive"))
      (node (ref "U2") (pin "2") (pinfunction "DM_2") (pintype "bidirectional"))
      (node (ref "Z2") (pin "1") (pinfunction "1_1") (pintype "passive"))
    )
    (net (code "65") (name "Net-(U2-DP)") (class "Default")
      (node (ref "R10") (pin "2") (pinfunction "2_2") (pintype "passive"))
      (node (ref "U2") (pin "3") (pinfunction "DP_3") (pintype "bidirectional"))
      (node (ref "Z1") (pin "1") (pinfunction "1_1") (pintype "passive"))
    )
    (net (code "66") (name "Net-(U2-VCC)") (class "Default")
      (node (ref "F1") (pin "1") (pinfunction "1_1") (pintype "bidirectional"))
      (node (ref "U2") (pin "1") (pinfunction "VCC_1") (pintype "bidirectional"))
    )
    (net (code "67") (name "POE_VIN+") (class "Default")
      (node (ref "D3") (pin "C") (pinfunction "C_C") (pintype "passive"))
      (node (ref "U$7") (pin "P5") (pinfunction "VIN+1_P5") (pintype "power_in"))
      (node (ref "U$7") (pin "P6") (pinfunction "VIN+2_P6") (pintype "power_in"))
      (node (ref "U1") (pin "P$9") (pinfunction "V+_P$9") (pintype "bidirectional"))
    )
    (net (code "68") (name "POE_VIN-") (class "Default")
      (node (ref "D3") (pin "A") (pinfunction "A_A") (pintype "passive"))
      (node (ref "U$7") (pin "P7") (pinfunction "VIN-1_P7") (pintype "power_in"))
      (node (ref "U$7") (pin "P8") (pinfunction "VIN-2_P8") (pintype "power_in"))
      (node (ref "U1") (pin "P$10") (pinfunction "V-_P$10") (pintype "bidirectional"))
    )
    (net (code "69") (name "RD+") (class "Default")
      (node (ref "IC1") (pin "14") (pinfunction "USBDP_14") (pintype "bidirectional"))
      (node (ref "R10") (pin "1") (pinfunction "1_1") (pintype "passive"))
    )
    (net (code "70") (name "RD-") (class "Default")
      (node (ref "IC1") (pin "15") (pinfunction "USBDM_15") (pintype "bidirectional"))
      (node (ref "R11") (pin "1") (pinfunction "1_1") (pintype "passive"))
    )
    (net (code "71") (name "RESET") (class "Default")
      (node (ref "C10") (pin "1") (pinfunction "1_1") (pintype "passive"))
      (node (ref "FTDI-RESET") (pin "2") (pinfunction "2_2") (pintype "passive"))
      (node (ref "IC2") (pin "4") (pinfunction "~{RESET}_4") (pintype "bidirectional"))
      (node (ref "IC3") (pin "3") (pinfunction "/MR_3") (pintype "input"))
      (node (ref "JP1") (pin "2") (pinfunction "2_2") (pintype "passive"))
      (node (ref "R15") (pin "1") (pinfunction "1_1") (pintype "passive"))
    )
    (net (code "72") (name "RXIN") (class "Default")
      (node (ref "IC4") (pin "5") (pinfunction "RXN_5") (pintype "passive"))
      (node (ref "RN1") (pin "6") (pinfunction "2_6") (pintype "passive"))
    )
    (net (code "73") (name "RXIP") (class "Default")
      (node (ref "IC4") (pin "6") (pinfunction "RXP_6") (pintype "passive"))
      (node (ref "RN1") (pin "5") (pinfunction "2_5") (pintype "passive"))
    )
    (net (code "74") (name "SCLK") (class "Default")
      (node (ref "C26") (pin "2") (pinfunction "2_2") (pintype "passive"))
      (node (ref "J5") (pin "7") (pinfunction "7_7") (pintype "passive"))
      (node (ref "R17") (pin "1") (pinfunction "1_1") (pintype "passive"))
    )
    (net (code "75") (name "TXON") (class "Default")
      (node (ref "IC4") (pin "1") (pinfunction "TXN_1") (pintype "passive"))
      (node (ref "RN1") (pin "8") (pinfunction "2_8") (pintype "passive"))
    )
    (net (code "76") (name "TXOP") (class "Default")
      (node (ref "IC4") (pin "2") (pinfunction "TXP_2") (pintype "passive"))
      (node (ref "RN1") (pin "7") (pinfunction "2_7") (pintype "passive"))
    )
    (net (code "77") (name "USBRXD") (class "Default")
      (node (ref "IC1") (pin "30") (pinfunction "TXD_30") (pintype "output"))
      (node (ref "R9") (pin "1") (pinfunction "1_1") (pintype "passive"))
    )
    (net (code "78") (name "USBTXD") (class "Default")
      (node (ref "IC1") (pin "2") (pinfunction "RXD_2") (pintype "input"))
      (node (ref "R8") (pin "1") (pinfunction "1_1") (pintype "passive"))
    )
    (net (code "79") (name "USBVCC") (class "Default")
      (node (ref "D4") (pin "1") (pinfunction "CA_1") (pintype "passive"))
      (node (ref "USBVCC") (pin "1") (pinfunction "1_1") (pintype "passive"))
    )
    (net (code "80") (name "VIN") (class "Default")
      (node (ref "C1") (pin "+") (pinfunction "+_+") (pintype "passive"))
      (node (ref "C2") (pin "1") (pinfunction "1_1") (pintype "passive"))
      (node (ref "C31") (pin "1") (pinfunction "1_1") (pintype "passive"))
      (node (ref "D6") (pin "1") (pinfunction "CA_1") (pintype "passive"))
      (node (ref "IC5") (pin "P$1") (pinfunction "VIN_P$1") (pintype "bidirectional"))
      (node (ref "L1") (pin "2") (pinfunction "2_2") (pintype "passive"))
      (node (ref "L2") (pin "2") (pinfunction "2_2") (pintype "passive"))
    )
    (net (code "81") (name "WIZRST") (class "Default")
      (node (ref "IC3") (pin "2") (pinfunction "/RESET_2") (pintype "output"))
      (node (ref "IC4") (pin "37") (pinfunction "RST_N_37") (pintype "passive"))
    )
    (net (code "82") (name "unconnected-(IC1-3V3OUT-Pad16)") (class "Default")
      (node (ref "IC1") (pin "16") (pinfunction "3V3OUT_16") (pintype "output"))
    )
    (net (code "83") (name "unconnected-(IC1-CBUS0-Pad22)") (class "Default")
      (node (ref "IC1") (pin "22") (pinfunction "CBUS0_22") (pintype "bidirectional"))
    )
    (net (code "84") (name "unconnected-(IC1-CBUS1-Pad21)") (class "Default")
      (node (ref "IC1") (pin "21") (pinfunction "CBUS1_21") (pintype "bidirectional"))
    )
    (net (code "85") (name "unconnected-(IC1-CBUS2-Pad10)") (class "Default")
      (node (ref "IC1") (pin "10") (pinfunction "CBUS2_10") (pintype "bidirectional"))
    )
    (net (code "86") (name "unconnected-(IC1-CBUS3-Pad11)") (class "Default")
      (node (ref "IC1") (pin "11") (pinfunction "CBUS3_11") (pintype "bidirectional"))
    )
    (net (code "87") (name "unconnected-(IC1-CBUS4-Pad9)") (class "Default")
      (node (ref "IC1") (pin "9") (pinfunction "CBUS4_9") (pintype "bidirectional"))
    )
    (net (code "88") (name "unconnected-(IC1-OSCI-Pad27)") (class "Default")
      (node (ref "IC1") (pin "27") (pinfunction "OSCI_27") (pintype "input"))
    )
    (net (code "89") (name "unconnected-(IC1-OSCO-Pad28)") (class "Default")
      (node (ref "IC1") (pin "28") (pinfunction "OSCO_28") (pintype "output"))
    )
    (net (code "90") (name "unconnected-(IC1-~{CTS}-Pad8)") (class "Default")
      (node (ref "IC1") (pin "8") (pinfunction "~{CTS}_8") (pintype "input"))
    )
    (net (code "91") (name "unconnected-(IC1-~{DCD}-Pad7)") (class "Default")
      (node (ref "IC1") (pin "7") (pinfunction "~{DCD}_7") (pintype "input"))
    )
    (net (code "92") (name "unconnected-(IC1-~{DSR}-Pad6)") (class "Default")
      (node (ref "IC1") (pin "6") (pinfunction "~{DSR}_6") (pintype "input"))
    )
    (net (code "93") (name "unconnected-(IC1-~{RESET}-Pad18)") (class "Default")
      (node (ref "IC1") (pin "18") (pinfunction "~{RESET}_18") (pintype "input"))
    )
    (net (code "94") (name "unconnected-(IC1-~{RI}-Pad3)") (class "Default")
      (node (ref "IC1") (pin "3") (pinfunction "~{RI}_3") (pintype "input"))
    )
    (net (code "95") (name "unconnected-(IC1-~{RTS}-Pad32)") (class "Default")
      (node (ref "IC1") (pin "32") (pinfunction "~{RTS}_32") (pintype "output"))
    )
    (net (code "96") (name "unconnected-(IC2-PA1(ADC1{slash}PCINT1)-Pad36)") (class "Default")
      (node (ref "IC2") (pin "36") (pinfunction "PA1(ADC1/PCINT1)_36") (pintype "bidirectional"))
    )
    (net (code "97") (name "unconnected-(IC2-PA5(ADC5{slash}PCINT5)-Pad32)") (class "Default")
      (node (ref "IC2") (pin "32") (pinfunction "PA5(ADC5/PCINT5)_32") (pintype "bidirectional"))
    )
    (net (code "98") (name "unconnected-(IC2-PA6(ADC6{slash}PCINT6)-Pad31)") (class "Default")
      (node (ref "IC2") (pin "31") (pinfunction "PA6(ADC6/PCINT6)_31") (pintype "bidirectional"))
    )
    (net (code "99") (name "unconnected-(IC2-PA7(ADC7{slash}PCINT7)-Pad30)") (class "Default")
      (node (ref "IC2") (pin "30") (pinfunction "PA7(ADC7/PCINT7)_30") (pintype "bidirectional"))
    )
    (net (code "100") (name "unconnected-(IC2-PB0(PCINT8{slash}XCK0{slash}T0)-Pad40)") (class "Default")
      (node (ref "IC2") (pin "40") (pinfunction "PB0(PCINT8/XCK0/T0)_40") (pintype "bidirectional"))
    )
    (net (code "101") (name "unconnected-(IC2-PB1(PCINT9{slash}CLKO{slash}T1)-Pad41)") (class "Default")
      (node (ref "IC2") (pin "41") (pinfunction "PB1(PCINT9/CLKO/T1)_41") (pintype "bidirectional"))
    )
    (net (code "102") (name "unconnected-(IC2-PC6(TOSC1{slash}PCINT22)-Pad25)") (class "Default")
      (node (ref "IC2") (pin "25") (pinfunction "PC6(TOSC1/PCINT22)_25") (pintype "bidirectional"))
    )
    (net (code "103") (name "unconnected-(IC2-PC7(TOSC2{slash}PCINT23)-Pad26)") (class "Default")
      (node (ref "IC2") (pin "26") (pinfunction "PC7(TOSC2/PCINT23)_26") (pintype "bidirectional"))
    )
    (net (code "104") (name "unconnected-(IC4-DNC-Pad7)") (class "Default")
      (node (ref "IC4") (pin "7") (pinfunction "DNC_7") (pintype "passive"))
    )
    (net (code "105") (name "unconnected-(IC4-DUPLED-Pad26)") (class "Default")
      (node (ref "IC4") (pin "26") (pinfunction "DUPLED_26") (pintype "passive"))
    )
    (net (code "106") (name "unconnected-(IC4-NC-Pad12)") (class "Default")
      (node (ref "IC4") (pin "12") (pinfunction "NC_12") (pintype "passive"))
    )
    (net (code "107") (name "unconnected-(IC4-NC-Pad13)") (class "Default")
      (node (ref "IC4") (pin "13") (pinfunction "NC_13") (pintype "passive"))
    )
    (net (code "108") (name "unconnected-(IC4-NC-Pad46)") (class "Default")
      (node (ref "IC4") (pin "46") (pinfunction "NC_46") (pintype "passive"))
    )
    (net (code "109") (name "unconnected-(IC4-NC-Pad47)") (class "Default")
      (node (ref "IC4") (pin "47") (pinfunction "NC_47") (pintype "passive"))
    )
    (net (code "110") (name "unconnected-(IC4-PMODE0-Pad45)") (class "Default")
      (node (ref "IC4") (pin "45") (pinfunction "PMODE0_45") (pintype "passive"))
    )
    (net (code "111") (name "unconnected-(IC4-PMODE1-Pad44)") (class "Default")
      (node (ref "IC4") (pin "44") (pinfunction "PMODE1_44") (pintype "passive"))
    )
    (net (code "112") (name "unconnected-(IC4-PMODE2-Pad43)") (class "Default")
      (node (ref "IC4") (pin "43") (pinfunction "PMODE2_43") (pintype "passive"))
    )
    (net (code "113") (name "unconnected-(IC4-RSVD-Pad23)") (class "Default")
      (node (ref "IC4") (pin "23") (pinfunction "RSVD_23") (pintype "passive"))
    )
    (net (code "114") (name "unconnected-(IC4-RSVD-Pad38)") (class "Default")
      (node (ref "IC4") (pin "38") (pinfunction "RSVD_38") (pintype "passive"))
    )
    (net (code "115") (name "unconnected-(IC4-RSVD-Pad39)") (class "Default")
      (node (ref "IC4") (pin "39") (pinfunction "RSVD_39") (pintype "passive"))
    )
    (net (code "116") (name "unconnected-(IC4-RSVD-Pad40)") (class "Default")
      (node (ref "IC4") (pin "40") (pinfunction "RSVD_40") (pintype "passive"))
    )
    (net (code "117") (name "unconnected-(IC4-RSVD-Pad41)") (class "Default")
      (node (ref "IC4") (pin "41") (pinfunction "RSVD_41") (pintype "passive"))
    )
    (net (code "118") (name "unconnected-(IC4-RSVD-Pad42)") (class "Default")
      (node (ref "IC4") (pin "42") (pinfunction "RSVD_42") (pintype "passive"))
    )
    (net (code "119") (name "unconnected-(IC4-SPDLED-Pad24)") (class "Default")
      (node (ref "IC4") (pin "24") (pinfunction "SPDLED_24") (pintype "passive"))
    )
    (net (code "120") (name "unconnected-(IC4-VBG-Pad18)") (class "Default")
      (node (ref "IC4") (pin "18") (pinfunction "VBG_18") (pintype "passive"))
    )
    (net (code "121") (name "unconnected-(U$7-ADJ-PadP4)") (class "Default")
      (node (ref "U$7") (pin "P4") (pinfunction "ADJ_P4") (pintype "input"))
    )
    (net (code "122") (name "unconnected-(U2-ID-Pad4)") (class "Default")
      (node (ref "U2") (pin "4") (pinfunction "ID_4") (pintype "bidirectional"))
    )
  )
)
